# 08_AUDIO.net
KiCad netlist of a schematic drawn in Altium Designer
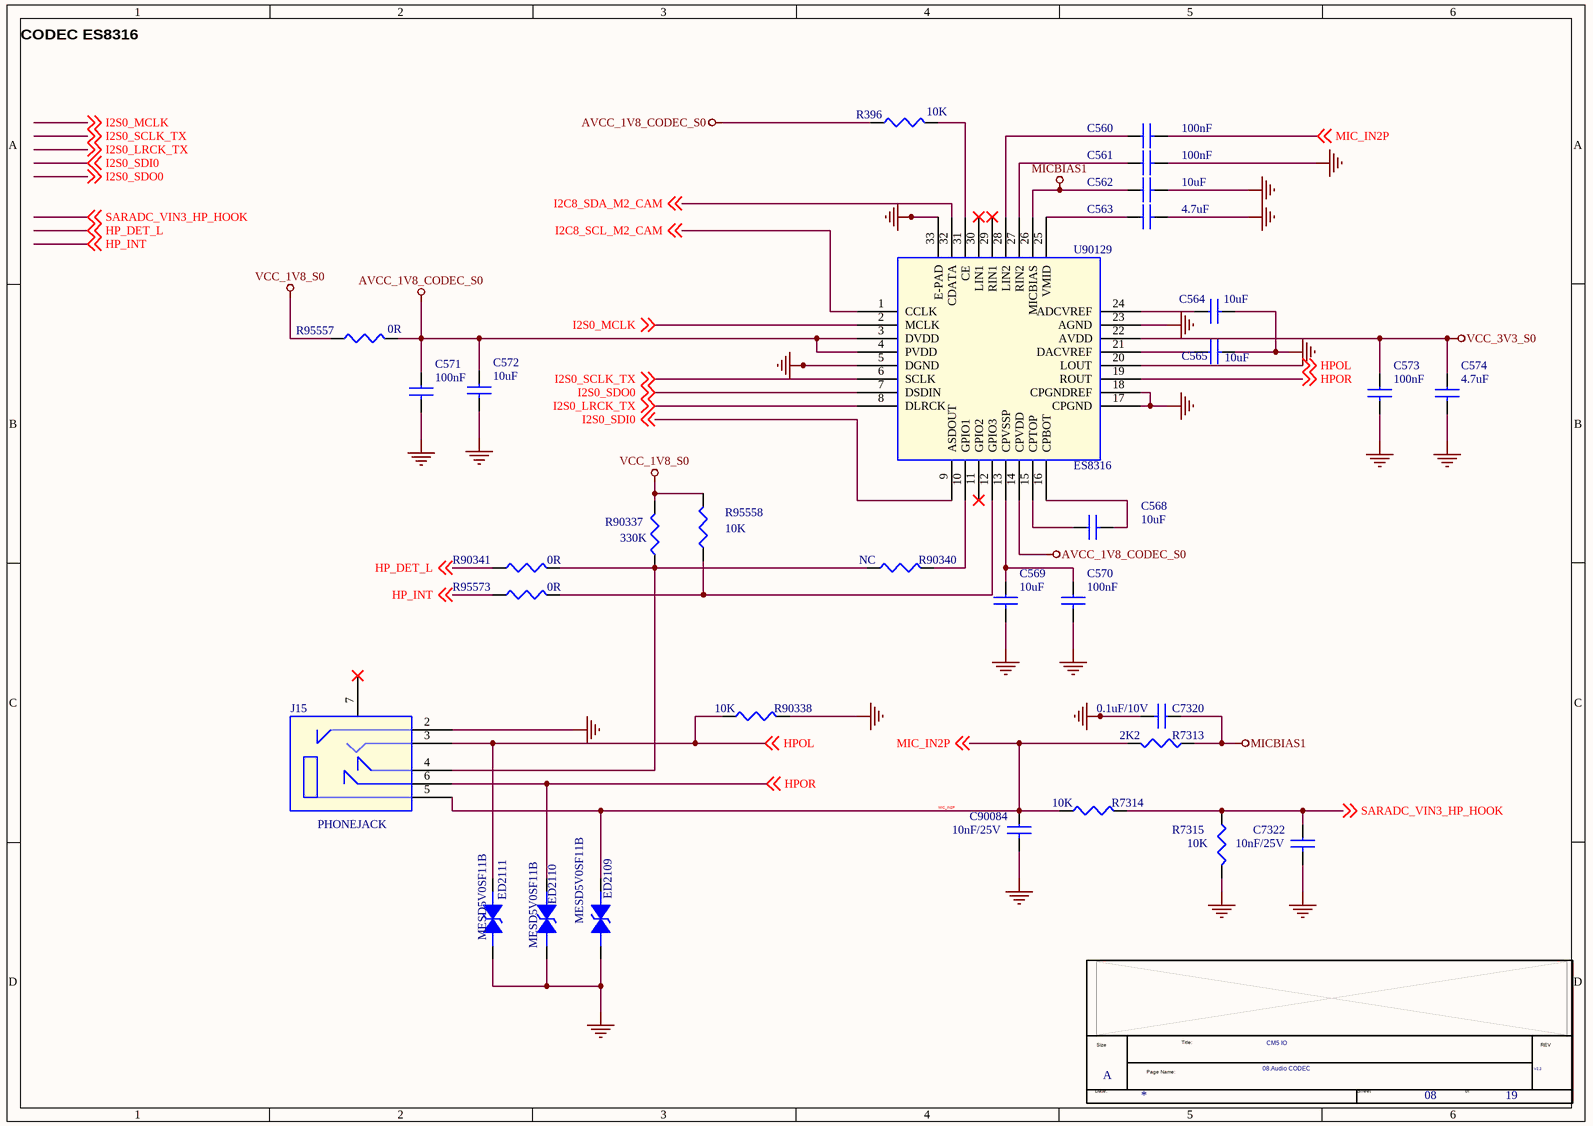
[diagram p0: 08_AUDIO.SchDoc]

(export (version "E")
  (design (tool "Eeschema 10.0.6"))
  (components
    (comp (ref "*")
      (value "radxa_1010")
      (fields
        (field (name "DOC") "08.Audio CODEC")
        (field (name "REVCODE") "V2.2")
        (field (name "TITLE") "CM5 IO")
        (field (name "PAGE SIZE") "A")
        (field (name "PAGE NUMBER") "08")
        (field (name "PAGE COUNT") "19")
      )
      (libsource (lib "*") (part "radxa_1010"))
    )
    (comp (ref "C560")
      (value "100nF")
      (footprint "C0402")
      (description "cap,100.00nF,+/-10%,16V,X5R,C0402")
      (fields
        (field (name "VOLTAGE") "16V")
        (field (name "MANUFACTURER") "TDK")
        (field (name "CREATED BY") "JJJ")
      )
      (libsource (lib "*") (part "CAP NP_0_Dup2"))
    )
    (comp (ref "C561")
      (value "100nF")
      (footprint "C0402")
      (description "cap,100.00nF,+/-10%,16V,X5R,C0402")
      (fields
        (field (name "VOLTAGE") "16V")
        (field (name "TOLERANCE") "10%")
        (field (name "CREATED BY") "JJJ")
      )
      (libsource (lib "*") (part "CAP NP_0_Dup2"))
    )
    (comp (ref "C562")
      (value "10uF")
      (footprint "C0603")
      (description "cap,10.00uF,+/-10%,10V,X5R,C0805")
      (fields
        (field (name "VOLTAGE") "10V")
        (field (name "MANUFACTURER") "TDK")
        (field (name "CREATED BY") "JJJ")
      )
      (libsource (lib "*") (part "CAP NP_0_Dup2"))
    )
    (comp (ref "C563")
      (value "4.7uF")
      (footprint "C0402")
      (description "cap,4.70uF,+/-10%,10V,X5R,C0603")
      (fields
        (field (name "VOLTAGE") "10V")
        (field (name "MANUFACTURER") "TDK")
        (field (name "CREATED BY") "JJJ")
      )
      (libsource (lib "*") (part "CAP NP_0_Dup2"))
    )
    (comp (ref "C564")
      (value "10uF")
      (footprint "C0603")
      (description "cap,10.00uF,+/-10%,10V,X5R,C0805")
      (fields
        (field (name "VOLTAGE") "10V")
        (field (name "MANUFACTURER") "TDK")
        (field (name "CREATED BY") "JJJ")
      )
      (libsource (lib "*") (part "CAP NP_0_Dup2"))
    )
    (comp (ref "C565")
      (value "10uF")
      (footprint "C0603")
      (description "cap,10.00uF,+/-10%,10V,X5R,C0805")
      (fields
        (field (name "VOLTAGE") "10V")
        (field (name "MANUFACTURER") "TDK")
        (field (name "CREATED BY") "JJJ")
      )
      (libsource (lib "*") (part "CAP NP_0_Dup2"))
    )
    (comp (ref "C568")
      (value "10uF")
      (footprint "C0603")
      (description "cap,10.00uF,+/-10%,10V,X5R,C0805")
      (fields
        (field (name "VOLTAGE") "10V")
        (field (name "TOLERANCE") "10%")
        (field (name "CREATED BY") "JJJ")
      )
      (libsource (lib "*") (part "CAP NP_0_Dup2"))
    )
    (comp (ref "C569")
      (value "10uF")
      (footprint "C0603")
      (description "cap,10.00uF,+/-10%,10V,X5R,C0805")
      (fields
        (field (name "VOLTAGE") "10V")
        (field (name "TOLERANCE") "10%")
        (field (name "CREATED BY") "JJJ")
      )
      (libsource (lib "*") (part "CAP NP_0_Dup2"))
    )
    (comp (ref "C570")
      (value "100nF")
      (footprint "C0402")
      (description "cap,100.00nF,+/-10%,16V,X5R,C0402")
      (fields
        (field (name "VOLTAGE") "16V")
        (field (name "MANUFACTURER") "TDK")
        (field (name "CREATED BY") "JJJ")
      )
      (libsource (lib "*") (part "CAP NP_0_Dup2"))
    )
    (comp (ref "C571")
      (value "100nF")
      (footprint "C0402")
      (description "cap,100.00nF,+/-10%,16V,X5R,C0402")
      (fields
        (field (name "VOLTAGE") "16V")
        (field (name "MANUFACTURER") "TDK")
        (field (name "CREATED BY") "JJJ")
      )
      (libsource (lib "*") (part "CAP NP_0_Dup2"))
    )
    (comp (ref "C572")
      (value "10uF")
      (footprint "C0603")
      (description "cap,10.00uF,+/-10%,10V,X5R,C0805")
      (fields
        (field (name "VOLTAGE") "10V")
        (field (name "MANUFACTURER") "TDK")
        (field (name "CREATED BY") "JJJ")
      )
      (libsource (lib "*") (part "CAP NP_0_Dup2"))
    )
    (comp (ref "C573")
      (value "100nF")
      (footprint "C0402")
      (description "cap,100.00nF,+/-10%,16V,X5R,C0402")
      (fields
        (field (name "VOLTAGE") "16V")
        (field (name "MANUFACTURER") "TDK")
        (field (name "CREATED BY") "JJJ")
      )
      (libsource (lib "*") (part "CAP NP_0_Dup2"))
    )
    (comp (ref "C574")
      (value "4.7uF")
      (footprint "C0402")
      (description "cap,4.70uF,+/-10%,10V,X5R,C0603")
      (fields
        (field (name "VOLTAGE") "10V")
        (field (name "TOLERANCE") "10%")
        (field (name "CREATED BY") "JJJ")
      )
      (libsource (lib "*") (part "CAP NP_0_Dup2"))
    )
    (comp (ref "C7320")
      (value "0.1uF/10V")
      (footprint "C0402")
      (description "RoHS CHIP CAP 0.1uF +10/-10% X7R")
      (libsource (lib "*") (part "CAP"))
    )
    (comp (ref "C7322")
      (value "10nF/25V")
      (footprint "C0402")
      (description "RoHS CHIP CAP 0.01uF +10/-10% X7R")
      (libsource (lib "*") (part "CAP"))
    )
    (comp (ref "C90084")
      (value "10nF/25V")
      (footprint "C0201")
      (description "RoHS CHIP CAP 0.01uF +10/-10% X7R")
      (libsource (lib "*") (part "CAP"))
    )
    (comp (ref "ED2109")
      (value "MESD5V0SF11B")
      (footprint "E0402N")
      (description "ESD Component,5V,30P,SMD,0402")
      (libsource (lib "*") (part "TVS"))
    )
    (comp (ref "ED2110")
      (value "MESD5V0SF11B")
      (footprint "E0402N")
      (description "ESD Component,5V,30P,SMD,0402")
      (libsource (lib "*") (part "TVS"))
    )
    (comp (ref "ED2111")
      (value "MESD5V0SF11B")
      (footprint "E0402N")
      (description "ESD Component,5V,30P,SMD,0402")
      (libsource (lib "*") (part "TVS"))
    )
    (comp (ref "J15")
      (value "PHONEJACK")
      (footprint "PJ-327A")
      (description "耳插")
      (libsource (lib "*") (part "PHONEJACK STEREO SW_0"))
    )
    (comp (ref "R396")
      (value "10K")
      (footprint "R0402")
      (description "通用厚膜电阻,33R,+/-5%,R0402,1/16W.")
      (fields
        (field (name "TOLERANCE") "5%")
        (field (name "MANUFACTURER") "YAGEO")
        (field (name "CREATED BY") "YTL")
      )
      (libsource (lib "*") (part "RESISTOR_1_Dup1"))
    )
    (comp (ref "R7313")
      (value "2K2")
      (footprint "R0402")
      (description "ROHS CHIP RES 2K2 1/16W 5%")
      (libsource (lib "*") (part "RESISTOR"))
    )
    (comp (ref "R7314")
      (value "10K")
      (footprint "R0402")
      (description "ROHS CHIP RES 0R 1/16W 5%")
      (libsource (lib "*") (part "RESISTOR"))
    )
    (comp (ref "R7315")
      (value "10K")
      (footprint "R0402")
      (description "ROHS CHIP RES 0R 1/16W 5%")
      (libsource (lib "*") (part "RESISTOR"))
    )
    (comp (ref "R90337")
      (value "330K")
      (footprint "R0201")
      (description "ROHS CHIP RES 0R 1/16W 5%")
      (libsource (lib "*") (part "RESISTOR"))
    )
    (comp (ref "R90338")
      (value "10K")
      (footprint "R0201")
      (description "ROHS CHIP RES 0R 1/16W 5%")
      (libsource (lib "*") (part "RESISTOR"))
    )
    (comp (ref "R90340")
      (value "NC")
      (footprint "R0201")
      (description "ROHS CHIP RES 0R 1/16W 5%")
      (libsource (lib "*") (part "RESISTOR"))
    )
    (comp (ref "R90341")
      (value "0R")
      (footprint "R0201")
      (description "ROHS CHIP RES 0R 1/16W 5%")
      (libsource (lib "*") (part "RESISTOR"))
    )
    (comp (ref "R95557")
      (value "0R")
      (footprint "R0402")
      (description "通用厚膜电阻,33R,+/-5%,R0402,1/16W.")
      (fields
        (field (name "TOLERANCE") "5%")
        (field (name "MANUFACTURER") "YAGEO")
        (field (name "CREATED BY") "YTL")
      )
      (libsource (lib "*") (part "RESISTOR_1_Dup1"))
    )
    (comp (ref "R95558")
      (value "10K")
      (footprint "R0201")
      (description "ROHS CHIP RES 0R 1/16W 5%")
      (libsource (lib "*") (part "RESISTOR"))
    )
    (comp (ref "R95573")
      (value "0R")
      (footprint "R0201")
      (description "ROHS CHIP RES 0R 1/16W 5%")
      (libsource (lib "*") (part "RESISTOR"))
    )
    (comp (ref "U90129")
      (value "ES8316")
      (footprint "QFN32P4X4")
      (description "Low Power Audio CODEC")
      (fields (field (name "MANUFACTURER") "Everest（顺芯）") (field (name "CREATED BY") "JJJ"))
      (libsource (lib "*") (part "CODEC_ES8316"))
    )
  )
  (nets
    (net (code "1") (name "AVCC_1V8_CODEC_S0") (class "Default")
      (node (ref "C571") (pin "1") (pinfunction "1_1") (pintype "passive"))
      (node (ref "C572") (pin "1") (pinfunction "1_1") (pintype "passive"))
      (node (ref "R396") (pin "1") (pinfunction "1_1") (pintype "passive"))
      (node (ref "R95557") (pin "2") (pinfunction "2_2") (pintype "passive"))
      (node (ref "U90129") (pin "14") (pinfunction "CPVDD_14") (pintype "passive"))
      (node (ref "U90129") (pin "3") (pinfunction "DVDD_3") (pintype "passive"))
      (node (ref "U90129") (pin "4") (pinfunction "PVDD_4") (pintype "passive"))
    )
    (net (code "2") (name "GND") (class "Default")
      (node (ref "C561") (pin "2") (pinfunction "2_2") (pintype "passive"))
      (node (ref "C562") (pin "2") (pinfunction "2_2") (pintype "passive"))
      (node (ref "C563") (pin "2") (pinfunction "2_2") (pintype "passive"))
      (node (ref "C564") (pin "2") (pinfunction "2_2") (pintype "passive"))
      (node (ref "C565") (pin "2") (pinfunction "2_2") (pintype "passive"))
      (node (ref "C569") (pin "2") (pinfunction "2_2") (pintype "passive"))
      (node (ref "C570") (pin "2") (pinfunction "2_2") (pintype "passive"))
      (node (ref "C571") (pin "2") (pinfunction "2_2") (pintype "passive"))
      (node (ref "C572") (pin "2") (pinfunction "2_2") (pintype "passive"))
      (node (ref "C573") (pin "2") (pinfunction "2_2") (pintype "passive"))
      (node (ref "C574") (pin "2") (pinfunction "2_2") (pintype "passive"))
      (node (ref "C7320") (pin "2") (pinfunction "2_2") (pintype "passive"))
      (node (ref "C7322") (pin "2") (pinfunction "2_2") (pintype "passive"))
      (node (ref "C90084") (pin "2") (pinfunction "2_2") (pintype "passive"))
      (node (ref "ED2109") (pin "2") (pinfunction "2_2") (pintype "passive"))
      (node (ref "ED2110") (pin "2") (pinfunction "2_2") (pintype "passive"))
      (node (ref "ED2111") (pin "2") (pinfunction "2_2") (pintype "passive"))
      (node (ref "J15") (pin "2") (pinfunction "DH_2") (pintype "passive"))
      (node (ref "R7315") (pin "1") (pinfunction "1_1") (pintype "passive"))
      (node (ref "R90338") (pin "1") (pinfunction "1_1") (pintype "passive"))
      (node (ref "U90129") (pin "17") (pinfunction "CPGND_17") (pintype "passive"))
      (node (ref "U90129") (pin "18") (pinfunction "CPGNDREF_18") (pintype "passive"))
      (node (ref "U90129") (pin "23") (pinfunction "AGND_23") (pintype "passive"))
      (node (ref "U90129") (pin "33") (pinfunction "E-PAD_33") (pintype "passive"))
      (node (ref "U90129") (pin "5") (pinfunction "DGND_5") (pintype "passive"))
    )
    (net (code "3") (name "HPOL") (class "Default")
      (node (ref "ED2111") (pin "1") (pinfunction "1_1") (pintype "passive"))
      (node (ref "J15") (pin "3") (pinfunction "R_3") (pintype "passive"))
      (node (ref "R90338") (pin "2") (pinfunction "2_2") (pintype "passive"))
      (node (ref "U90129") (pin "20") (pinfunction "LOUT_20") (pintype "passive"))
    )
    (net (code "4") (name "HPOR") (class "Default")
      (node (ref "ED2110") (pin "1") (pinfunction "1_1") (pintype "passive"))
      (node (ref "J15") (pin "6") (pinfunction "HP_6") (pintype "passive"))
      (node (ref "U90129") (pin "19") (pinfunction "ROUT_19") (pintype "passive"))
    )
    (net (code "5") (name "HP_DET_L") (class "Default")
      (node (ref "R90341") (pin "2") (pinfunction "2_2") (pintype "passive"))
    )
    (net (code "6") (name "HP_INT") (class "Default")
      (node (ref "R95573") (pin "2") (pinfunction "2_2") (pintype "passive"))
    )
    (net (code "7") (name "I2C8_SCL_M2_CAM") (class "Default")
      (node (ref "U90129") (pin "1") (pinfunction "CCLK_1") (pintype "passive"))
    )
    (net (code "8") (name "I2C8_SDA_M2_CAM") (class "Default")
      (node (ref "U90129") (pin "32") (pinfunction "CDATA_32") (pintype "passive"))
    )
    (net (code "9") (name "I2S0_LRCK_TX") (class "Default")
      (node (ref "U90129") (pin "8") (pinfunction "DLRCK_8") (pintype "passive"))
    )
    (net (code "10") (name "I2S0_MCLK") (class "Default")
      (node (ref "U90129") (pin "2") (pinfunction "MCLK_2") (pintype "passive"))
    )
    (net (code "11") (name "I2S0_SCLK_TX") (class "Default")
      (node (ref "U90129") (pin "6") (pinfunction "SCLK_6") (pintype "passive"))
    )
    (net (code "12") (name "I2S0_SDI0") (class "Default")
      (node (ref "U90129") (pin "9") (pinfunction "ASDOUT_9") (pintype "passive"))
    )
    (net (code "13") (name "I2S0_SDO0") (class "Default")
      (node (ref "U90129") (pin "7") (pinfunction "DSDIN_7") (pintype "passive"))
    )
    (net (code "14") (name "MICBIAS1") (class "Default")
      (node (ref "C562") (pin "1") (pinfunction "1_1") (pintype "passive"))
      (node (ref "C7320") (pin "1") (pinfunction "1_1") (pintype "passive"))
      (node (ref "R7313") (pin "2") (pinfunction "2_2") (pintype "passive"))
      (node (ref "U90129") (pin "26") (pinfunction "MICBIAS_26") (pintype "passive"))
    )
    (net (code "15") (name "MIC_IN2P") (class "Default")
      (node (ref "C560") (pin "2") (pinfunction "2_2") (pintype "passive"))
      (node (ref "C90084") (pin "1") (pinfunction "1_1") (pintype "passive"))
      (node (ref "ED2109") (pin "1") (pinfunction "1_1") (pintype "passive"))
      (node (ref "J15") (pin "5") (pinfunction "D_5") (pintype "passive"))
      (node (ref "R7313") (pin "1") (pinfunction "1_1") (pintype "passive"))
      (node (ref "R7314") (pin "2") (pinfunction "2_2") (pintype "passive"))
    )
    (net (code "16") (name "Net-(J15-L)") (class "Default")
      (node (ref "J15") (pin "4") (pinfunction "L_4") (pintype "passive"))
      (node (ref "R90337") (pin "2") (pinfunction "2_2") (pintype "passive"))
      (node (ref "R90340") (pin "2") (pinfunction "2_2") (pintype "passive"))
      (node (ref "R90341") (pin "1") (pinfunction "1_1") (pintype "passive"))
    )
    (net (code "17") (name "Net-(U90129-ADCVREF)") (class "Default")
      (node (ref "C564") (pin "1") (pinfunction "1_1") (pintype "passive"))
      (node (ref "U90129") (pin "24") (pinfunction "ADCVREF_24") (pintype "passive"))
    )
    (net (code "18") (name "Net-(U90129-CE)") (class "Default")
      (node (ref "R396") (pin "2") (pinfunction "2_2") (pintype "passive"))
      (node (ref "U90129") (pin "31") (pinfunction "CE_31") (pintype "passive"))
    )
    (net (code "19") (name "Net-(U90129-CPBOT)") (class "Default")
      (node (ref "C568") (pin "2") (pinfunction "2_2") (pintype "passive"))
      (node (ref "U90129") (pin "16") (pinfunction "CPBOT_16") (pintype "passive"))
    )
    (net (code "20") (name "Net-(U90129-CPTOP)") (class "Default")
      (node (ref "C568") (pin "1") (pinfunction "1_1") (pintype "passive"))
      (node (ref "U90129") (pin "15") (pinfunction "CPTOP_15") (pintype "passive"))
    )
    (net (code "21") (name "Net-(U90129-CPVSSP)") (class "Default")
      (node (ref "C569") (pin "1") (pinfunction "1_1") (pintype "passive"))
      (node (ref "C570") (pin "1") (pinfunction "1_1") (pintype "passive"))
      (node (ref "U90129") (pin "13") (pinfunction "CPVSSP_13") (pintype "passive"))
    )
    (net (code "22") (name "Net-(U90129-DACVREF)") (class "Default")
      (node (ref "C565") (pin "1") (pinfunction "1_1") (pintype "passive"))
      (node (ref "U90129") (pin "21") (pinfunction "DACVREF_21") (pintype "passive"))
    )
    (net (code "23") (name "Net-(U90129-GPIO1)") (class "Default")
      (node (ref "R90340") (pin "1") (pinfunction "1_1") (pintype "passive"))
      (node (ref "U90129") (pin "10") (pinfunction "GPIO1_10") (pintype "passive"))
    )
    (net (code "24") (name "Net-(U90129-GPIO3)") (class "Default")
      (node (ref "R95558") (pin "2") (pinfunction "2_2") (pintype "passive"))
      (node (ref "R95573") (pin "1") (pinfunction "1_1") (pintype "passive"))
      (node (ref "U90129") (pin "12") (pinfunction "GPIO3_12") (pintype "passive"))
    )
    (net (code "25") (name "Net-(U90129-LIN2)") (class "Default")
      (node (ref "C560") (pin "1") (pinfunction "1_1") (pintype "passive"))
      (node (ref "U90129") (pin "28") (pinfunction "LIN2_28") (pintype "passive"))
    )
    (net (code "26") (name "Net-(U90129-RIN2)") (class "Default")
      (node (ref "C561") (pin "1") (pinfunction "1_1") (pintype "passive"))
      (node (ref "U90129") (pin "27") (pinfunction "RIN2_27") (pintype "passive"))
    )
    (net (code "27") (name "Net-(U90129-VMID)") (class "Default")
      (node (ref "C563") (pin "1") (pinfunction "1_1") (pintype "passive"))
      (node (ref "U90129") (pin "25") (pinfunction "VMID_25") (pintype "passive"))
    )
    (net (code "28") (name "SARADC_VIN3_HP_HOOK") (class "Default")
      (node (ref "C7322") (pin "1") (pinfunction "1_1") (pintype "passive"))
      (node (ref "R7314") (pin "1") (pinfunction "1_1") (pintype "passive"))
      (node (ref "R7315") (pin "2") (pinfunction "2_2") (pintype "passive"))
    )
    (net (code "29") (name "VCC_1V8_S0") (class "Default")
      (node (ref "R90337") (pin "1") (pinfunction "1_1") (pintype "passive"))
      (node (ref "R95557") (pin "1") (pinfunction "1_1") (pintype "passive"))
      (node (ref "R95558") (pin "1") (pinfunction "1_1") (pintype "passive"))
    )
    (net (code "30") (name "VCC_3V3_S0") (class "Default")
      (node (ref "C573") (pin "1") (pinfunction "1_1") (pintype "passive"))
      (node (ref "C574") (pin "1") (pinfunction "1_1") (pintype "passive"))
      (node (ref "U90129") (pin "22") (pinfunction "AVDD_22") (pintype "passive"))
    )
    (net (code "31") (name "unconnected-(J15-NC2-Pad7)") (class "Default")
      (node (ref "J15") (pin "7") (pinfunction "NC2_7") (pintype "passive+no_connect"))
    )
    (net (code "32") (name "unconnected-(U90129-GPIO2-Pad11)") (class "Default")
      (node (ref "U90129") (pin "11") (pinfunction "GPIO2_11") (pintype "passive+no_connect"))
    )
    (net (code "33") (name "unconnected-(U90129-LIN1-Pad30)") (class "Default")
      (node (ref "U90129") (pin "30") (pinfunction "LIN1_30") (pintype "passive+no_connect"))
    )
    (net (code "34") (name "unconnected-(U90129-RIN1-Pad29)") (class "Default")
      (node (ref "U90129") (pin "29") (pinfunction "RIN1_29") (pintype "passive+no_connect"))
    )
  )
)
